# Sheet1.net
KiCad netlist of a schematic drawn in Altium Designer
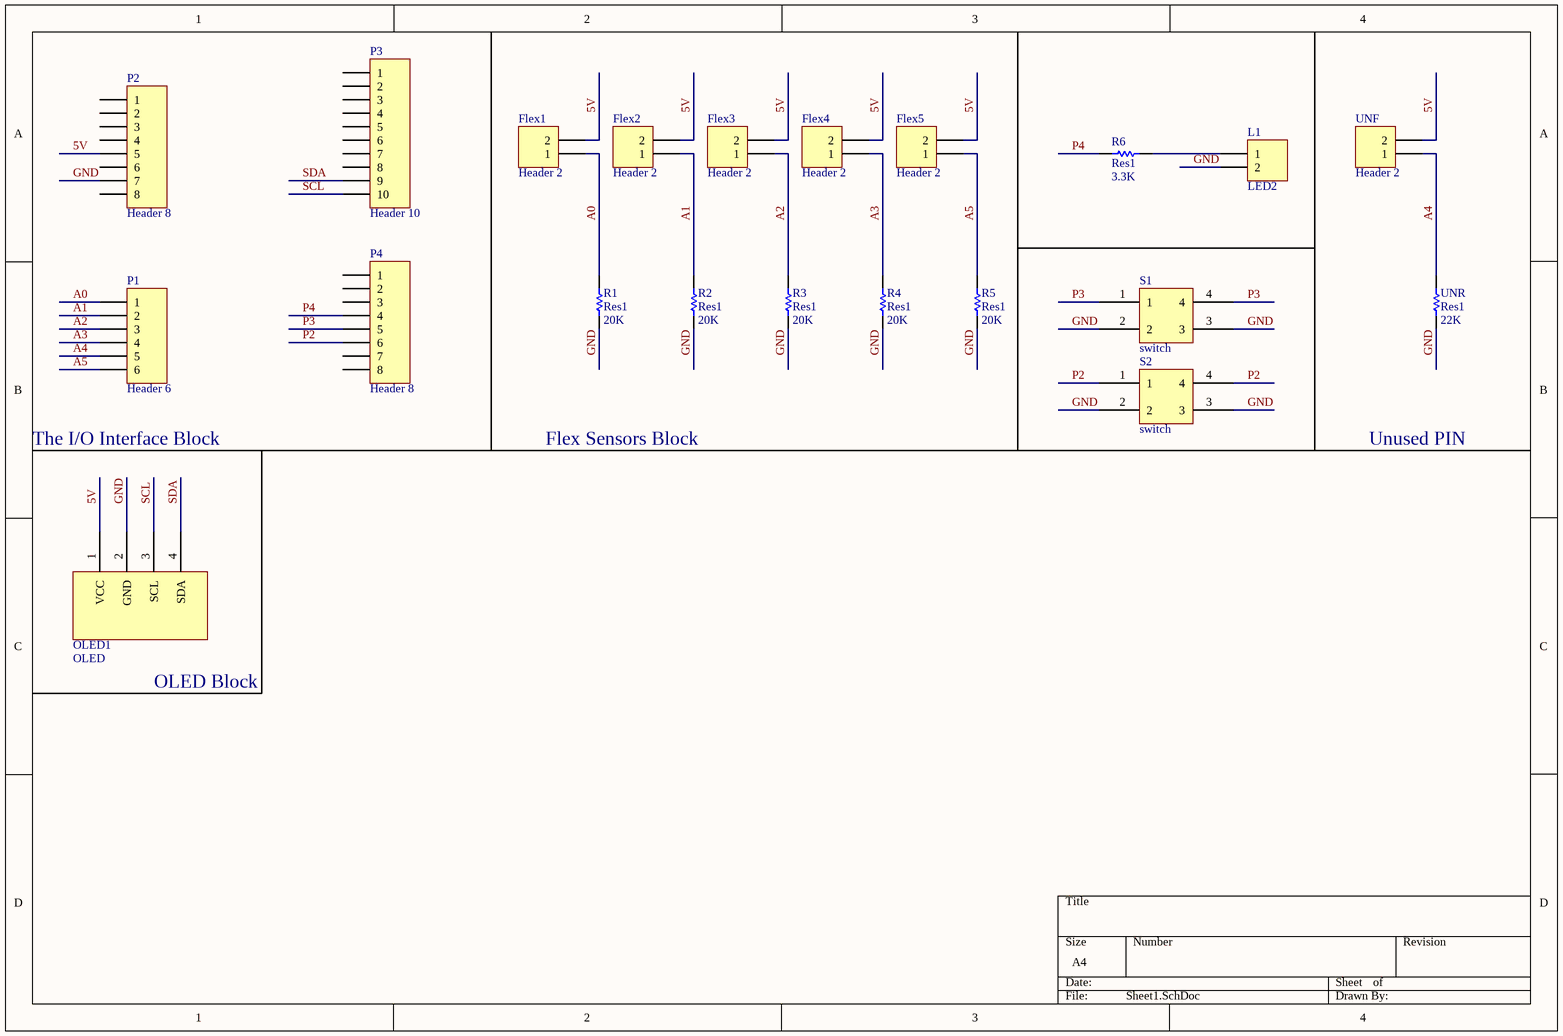
[diagram p0: Sheet1.SchDoc]

(export (version "E")
  (design (tool "Eeschema 10.0.6"))
  (components
    (comp (ref "Flex1")
      (value "Header 2")
      (footprint "HDR1X2")
      (description "Header, 2-Pin")
      (fields (field (name "PUBLISHER") "Altium Limited"))
      (libsource (lib "Miscellaneous Connectors") (part "Header 2"))
    )
    (comp (ref "Flex2")
      (value "Header 2")
      (footprint "HDR1X2")
      (description "Header, 2-Pin")
      (fields (field (name "PUBLISHER") "Altium Limited"))
      (libsource (lib "Miscellaneous Connectors") (part "Header 2"))
    )
    (comp (ref "Flex3")
      (value "Header 2")
      (footprint "HDR1X2")
      (description "Header, 2-Pin")
      (fields (field (name "PUBLISHER") "Altium Limited"))
      (libsource (lib "Miscellaneous Connectors") (part "Header 2"))
    )
    (comp (ref "Flex4")
      (value "Header 2")
      (footprint "HDR1X2")
      (description "Header, 2-Pin")
      (fields (field (name "PUBLISHER") "Altium Limited"))
      (libsource (lib "Miscellaneous Connectors") (part "Header 2"))
    )
    (comp (ref "Flex5")
      (value "Header 2")
      (footprint "HDR1X2")
      (description "Header, 2-Pin")
      (fields (field (name "PUBLISHER") "Altium Limited"))
      (libsource (lib "Miscellaneous Connectors") (part "Header 2"))
    )
    (comp (ref "L1")
      (value "LED2")
      (footprint "HDR1X2")
      (description "Header, 2-Pin")
      (fields (field (name "PUBLISHER") "Altium Limited"))
      (libsource (lib "") (part "Header 2_1"))
    )
    (comp (ref "OLED1") (value "OLED") (footprint "OLED") (libsource (lib "Schlib1") (part "OLED")))
    (comp (ref "P1")
      (value "Header 6")
      (footprint "HDR1X6")
      (description "Header, 6-Pin")
      (fields (field (name "PUBLISHER") "Altium Limited"))
      (libsource (lib "Miscellaneous Connectors") (part "Header 6"))
    )
    (comp (ref "P2")
      (value "Header 8")
      (footprint "HDR1X8")
      (description "Header, 8-Pin")
      (fields (field (name "PUBLISHER") "Altium Limited"))
      (libsource (lib "Miscellaneous Connectors") (part "Header 8"))
    )
    (comp (ref "P3")
      (value "Header 10")
      (footprint "HDR1X10")
      (description "Header, 10-Pin")
      (fields (field (name "PUBLISHER") "Altium Limited"))
      (libsource (lib "Miscellaneous Connectors") (part "Header 10"))
    )
    (comp (ref "P4")
      (value "Header 8")
      (footprint "HDR1X8")
      (description "Header, 8-Pin")
      (fields (field (name "PUBLISHER") "Altium Limited"))
      (libsource (lib "Miscellaneous Connectors") (part "Header 8"))
    )
    (comp (ref "R1")
      (value "Res1")
      (footprint "AXIAL-0.3")
      (description "Resistor")
      (fields (field (name "ALTIUM_VALUE") "20K") (field (name "PUBLISHER") "Altium Limited"))
      (libsource (lib "Miscellaneous Devices") (part "Res1"))
    )
    (comp (ref "R2")
      (value "Res1")
      (footprint "AXIAL-0.3")
      (description "Resistor")
      (fields (field (name "ALTIUM_VALUE") "20K") (field (name "PUBLISHER") "Altium Limited"))
      (libsource (lib "Miscellaneous Devices") (part "Res1"))
    )
    (comp (ref "R3")
      (value "Res1")
      (footprint "AXIAL-0.3")
      (description "Resistor")
      (fields (field (name "ALTIUM_VALUE") "20K") (field (name "PUBLISHER") "Altium Limited"))
      (libsource (lib "Miscellaneous Devices") (part "Res1"))
    )
    (comp (ref "R4")
      (value "Res1")
      (footprint "AXIAL-0.3")
      (description "Resistor")
      (fields (field (name "ALTIUM_VALUE") "20K") (field (name "PUBLISHER") "Altium Limited"))
      (libsource (lib "Miscellaneous Devices") (part "Res1"))
    )
    (comp (ref "R5")
      (value "Res1")
      (footprint "AXIAL-0.3")
      (description "Resistor")
      (fields (field (name "ALTIUM_VALUE") "20K") (field (name "PUBLISHER") "Altium Limited"))
      (libsource (lib "Miscellaneous Devices") (part "Res1"))
    )
    (comp (ref "R6")
      (value "Res1")
      (footprint "AXIAL-0.3")
      (description "Resistor")
      (fields (field (name "ALTIUM_VALUE") "3.3K") (field (name "PUBLISHER") "Altium Limited"))
      (libsource (lib "Miscellaneous Devices") (part "Res1"))
    )
    (comp (ref "S1") (value "switch") (footprint "switch") (libsource (lib "Schlib1") (part "switch")))
    (comp (ref "S2") (value "switch") (footprint "switch") (libsource (lib "Schlib1") (part "switch")))
    (comp (ref "UNF")
      (value "Header 2")
      (footprint "HDR1X2")
      (description "Header, 2-Pin")
      (fields (field (name "PUBLISHER") "Altium Limited"))
      (libsource (lib "Miscellaneous Connectors") (part "Header 2"))
    )
    (comp (ref "UNR")
      (value "Res1")
      (footprint "AXIAL-0.3")
      (description "Resistor")
      (fields (field (name "ALTIUM_VALUE") "22K") (field (name "PUBLISHER") "Altium Limited"))
      (libsource (lib "Miscellaneous Devices") (part "Res1"))
    )
  )
  (nets
    (net (code "1") (name "/5V") (class "Default")
      (node (ref "Flex1") (pin "2") (pinfunction "2_2") (pintype "passive"))
      (node (ref "Flex2") (pin "2") (pinfunction "2_2") (pintype "passive"))
      (node (ref "Flex3") (pin "2") (pinfunction "2_2") (pintype "passive"))
      (node (ref "Flex4") (pin "2") (pinfunction "2_2") (pintype "passive"))
      (node (ref "Flex5") (pin "2") (pinfunction "2_2") (pintype "passive"))
      (node (ref "OLED1") (pin "1") (pinfunction "VCC_1") (pintype "passive"))
      (node (ref "P2") (pin "5") (pinfunction "5_5") (pintype "passive"))
      (node (ref "UNF") (pin "2") (pinfunction "2_2") (pintype "passive"))
    )
    (net (code "2") (name "/A0") (class "Default")
      (node (ref "Flex1") (pin "1") (pinfunction "1_1") (pintype "passive"))
      (node (ref "P1") (pin "1") (pinfunction "1_1") (pintype "passive"))
      (node (ref "R1") (pin "2") (pinfunction "2_2") (pintype "passive"))
    )
    (net (code "3") (name "/A1") (class "Default")
      (node (ref "Flex2") (pin "1") (pinfunction "1_1") (pintype "passive"))
      (node (ref "P1") (pin "2") (pinfunction "2_2") (pintype "passive"))
      (node (ref "R2") (pin "2") (pinfunction "2_2") (pintype "passive"))
    )
    (net (code "4") (name "/A2") (class "Default")
      (node (ref "Flex3") (pin "1") (pinfunction "1_1") (pintype "passive"))
      (node (ref "P1") (pin "3") (pinfunction "3_3") (pintype "passive"))
      (node (ref "R3") (pin "2") (pinfunction "2_2") (pintype "passive"))
    )
    (net (code "5") (name "/A3") (class "Default")
      (node (ref "Flex4") (pin "1") (pinfunction "1_1") (pintype "passive"))
      (node (ref "P1") (pin "4") (pinfunction "4_4") (pintype "passive"))
      (node (ref "R4") (pin "2") (pinfunction "2_2") (pintype "passive"))
    )
    (net (code "6") (name "/A4") (class "Default")
      (node (ref "P1") (pin "5") (pinfunction "5_5") (pintype "passive"))
      (node (ref "UNF") (pin "1") (pinfunction "1_1") (pintype "passive"))
      (node (ref "UNR") (pin "2") (pinfunction "2_2") (pintype "passive"))
    )
    (net (code "7") (name "/A5") (class "Default")
      (node (ref "Flex5") (pin "1") (pinfunction "1_1") (pintype "passive"))
      (node (ref "P1") (pin "6") (pinfunction "6_6") (pintype "passive"))
      (node (ref "R5") (pin "2") (pinfunction "2_2") (pintype "passive"))
    )
    (net (code "8") (name "/GND") (class "Default")
      (node (ref "L1") (pin "2") (pinfunction "2_2") (pintype "passive"))
      (node (ref "OLED1") (pin "2") (pinfunction "GND_2") (pintype "passive"))
      (node (ref "P2") (pin "7") (pinfunction "7_7") (pintype "passive"))
      (node (ref "R1") (pin "1") (pinfunction "1_1") (pintype "passive"))
      (node (ref "R2") (pin "1") (pinfunction "1_1") (pintype "passive"))
      (node (ref "R3") (pin "1") (pinfunction "1_1") (pintype "passive"))
      (node (ref "R4") (pin "1") (pinfunction "1_1") (pintype "passive"))
      (node (ref "R5") (pin "1") (pinfunction "1_1") (pintype "passive"))
      (node (ref "S1") (pin "2") (pinfunction "2_2") (pintype "passive"))
      (node (ref "S1") (pin "3") (pinfunction "3_3") (pintype "passive"))
      (node (ref "S2") (pin "2") (pinfunction "2_2") (pintype "passive"))
      (node (ref "S2") (pin "3") (pinfunction "3_3") (pintype "passive"))
      (node (ref "UNR") (pin "1") (pinfunction "1_1") (pintype "passive"))
    )
    (net (code "9") (name "/P2") (class "Default")
      (node (ref "P4") (pin "6") (pinfunction "6_6") (pintype "passive"))
      (node (ref "S2") (pin "1") (pinfunction "1_1") (pintype "passive"))
      (node (ref "S2") (pin "4") (pinfunction "4_4") (pintype "passive"))
    )
    (net (code "10") (name "/P3") (class "Default")
      (node (ref "P4") (pin "5") (pinfunction "5_5") (pintype "passive"))
      (node (ref "S1") (pin "1") (pinfunction "1_1") (pintype "passive"))
      (node (ref "S1") (pin "4") (pinfunction "4_4") (pintype "passive"))
    )
    (net (code "11") (name "/P4") (class "Default")
      (node (ref "P4") (pin "4") (pinfunction "4_4") (pintype "passive"))
      (node (ref "R6") (pin "1") (pinfunction "1_1") (pintype "passive"))
    )
    (net (code "12") (name "/SCL") (class "Default")
      (node (ref "OLED1") (pin "3") (pinfunction "SCL_3") (pintype "passive"))
      (node (ref "P3") (pin "10") (pinfunction "10_10") (pintype "passive"))
    )
    (net (code "13") (name "/SDA") (class "Default")
      (node (ref "OLED1") (pin "4") (pinfunction "SDA_4") (pintype "passive"))
      (node (ref "P3") (pin "9") (pinfunction "9_9") (pintype "passive"))
    )
    (net (code "14") (name "Net-(L1-Pad1)") (class "Default")
      (node (ref "L1") (pin "1") (pinfunction "1_1") (pintype "passive"))
      (node (ref "R6") (pin "2") (pinfunction "2_2") (pintype "passive"))
    )
    (net (code "15") (name "unconnected-(P2-Pad1)") (class "Default")
      (node (ref "P2") (pin "1") (pinfunction "1_1") (pintype "passive"))
    )
    (net (code "16") (name "unconnected-(P2-Pad2)") (class "Default")
      (node (ref "P2") (pin "2") (pinfunction "2_2") (pintype "passive"))
    )
    (net (code "17") (name "unconnected-(P2-Pad3)") (class "Default")
      (node (ref "P2") (pin "3") (pinfunction "3_3") (pintype "passive"))
    )
    (net (code "18") (name "unconnected-(P2-Pad4)") (class "Default")
      (node (ref "P2") (pin "4") (pinfunction "4_4") (pintype "passive"))
    )
    (net (code "19") (name "unconnected-(P2-Pad6)") (class "Default")
      (node (ref "P2") (pin "6") (pinfunction "6_6") (pintype "passive"))
    )
    (net (code "20") (name "unconnected-(P2-Pad8)") (class "Default")
      (node (ref "P2") (pin "8") (pinfunction "8_8") (pintype "passive"))
    )
    (net (code "21") (name "unconnected-(P3-Pad1)") (class "Default")
      (node (ref "P3") (pin "1") (pinfunction "1_1") (pintype "passive"))
    )
    (net (code "22") (name "unconnected-(P3-Pad2)") (class "Default")
      (node (ref "P3") (pin "2") (pinfunction "2_2") (pintype "passive"))
    )
    (net (code "23") (name "unconnected-(P3-Pad3)") (class "Default")
      (node (ref "P3") (pin "3") (pinfunction "3_3") (pintype "passive"))
    )
    (net (code "24") (name "unconnected-(P3-Pad4)") (class "Default")
      (node (ref "P3") (pin "4") (pinfunction "4_4") (pintype "passive"))
    )
    (net (code "25") (name "unconnected-(P3-Pad5)") (class "Default")
      (node (ref "P3") (pin "5") (pinfunction "5_5") (pintype "passive"))
    )
    (net (code "26") (name "unconnected-(P3-Pad6)") (class "Default")
      (node (ref "P3") (pin "6") (pinfunction "6_6") (pintype "passive"))
    )
    (net (code "27") (name "unconnected-(P3-Pad7)") (class "Default")
      (node (ref "P3") (pin "7") (pinfunction "7_7") (pintype "passive"))
    )
    (net (code "28") (name "unconnected-(P3-Pad8)") (class "Default")
      (node (ref "P3") (pin "8") (pinfunction "8_8") (pintype "passive"))
    )
    (net (code "29") (name "unconnected-(P4-Pad1)") (class "Default")
      (node (ref "P4") (pin "1") (pinfunction "1_1") (pintype "passive"))
    )
    (net (code "30") (name "unconnected-(P4-Pad2)") (class "Default")
      (node (ref "P4") (pin "2") (pinfunction "2_2") (pintype "passive"))
    )
    (net (code "31") (name "unconnected-(P4-Pad3)") (class "Default")
      (node (ref "P4") (pin "3") (pinfunction "3_3") (pintype "passive"))
    )
    (net (code "32") (name "unconnected-(P4-Pad7)") (class "Default")
      (node (ref "P4") (pin "7") (pinfunction "7_7") (pintype "passive"))
    )
    (net (code "33") (name "unconnected-(P4-Pad8)") (class "Default")
      (node (ref "P4") (pin "8") (pinfunction "8_8") (pintype "passive"))
    )
  )
)
